# 4x_0805.net
KiCad netlist of a schematic drawn in EAGLE
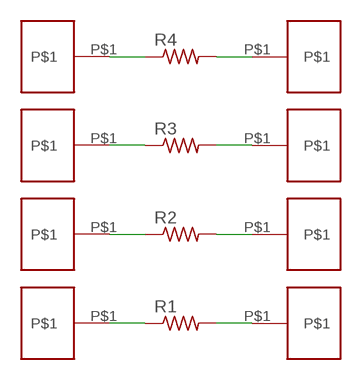
[diagram p0: schematic, sheet 1]

(export (version "E")
  (design (tool "Eeschema 10.0.6"))
  (components
    (comp (ref "R1")
      (value "R-US_R0805")
      (footprint "eagle-import:R0805")
      (libsource (lib "eagle-import") (part "R-US_R0805"))
    )
    (comp (ref "R2")
      (value "R-US_R0805")
      (footprint "eagle-import:R0805")
      (libsource (lib "eagle-import") (part "R-US_R0805"))
    )
    (comp (ref "R3")
      (value "R-US_R0805")
      (footprint "eagle-import:R0805")
      (libsource (lib "eagle-import") (part "R-US_R0805"))
    )
    (comp (ref "R4")
      (value "R-US_R0805")
      (footprint "eagle-import:R0805")
      (libsource (lib "eagle-import") (part "R-US_R0805"))
    )
    (comp (ref "U$1")
      (value "PAD100MIL")
      (footprint "eagle-import:100MIL_PAD")
      (libsource (lib "eagle-import") (part "PAD100MIL"))
    )
    (comp (ref "U$2")
      (value "PAD100MIL")
      (footprint "eagle-import:100MIL_PAD")
      (libsource (lib "eagle-import") (part "PAD100MIL"))
    )
    (comp (ref "U$3")
      (value "PAD100MIL")
      (footprint "eagle-import:100MIL_PAD")
      (libsource (lib "eagle-import") (part "PAD100MIL"))
    )
    (comp (ref "U$4")
      (value "PAD100MIL")
      (footprint "eagle-import:100MIL_PAD")
      (libsource (lib "eagle-import") (part "PAD100MIL"))
    )
    (comp (ref "U$5")
      (value "PAD100MIL")
      (footprint "eagle-import:100MIL_PAD")
      (libsource (lib "eagle-import") (part "PAD100MIL"))
    )
    (comp (ref "U$6")
      (value "PAD100MIL")
      (footprint "eagle-import:100MIL_PAD")
      (libsource (lib "eagle-import") (part "PAD100MIL"))
    )
    (comp (ref "U$7")
      (value "PAD100MIL")
      (footprint "eagle-import:100MIL_PAD")
      (libsource (lib "eagle-import") (part "PAD100MIL"))
    )
    (comp (ref "U$8")
      (value "PAD100MIL")
      (footprint "eagle-import:100MIL_PAD")
      (libsource (lib "eagle-import") (part "PAD100MIL"))
    )
  )
  (nets
    (net (code "1") (name "Net-(R1-Pad1)") (class "Default")
      (node (ref "R1") (pin "1") (pinfunction "1_1") (pintype "passive"))
      (node (ref "U$4") (pin "P$1") (pinfunction "P$1_P$1") (pintype "bidirectional"))
    )
    (net (code "2") (name "Net-(R1-Pad2)") (class "Default")
      (node (ref "R1") (pin "2") (pinfunction "2_2") (pintype "passive"))
      (node (ref "U$8") (pin "P$1") (pinfunction "P$1_P$1") (pintype "bidirectional"))
    )
    (net (code "3") (name "Net-(R2-Pad1)") (class "Default")
      (node (ref "R2") (pin "1") (pinfunction "1_1") (pintype "passive"))
      (node (ref "U$3") (pin "P$1") (pinfunction "P$1_P$1") (pintype "bidirectional"))
    )
    (net (code "4") (name "Net-(R2-Pad2)") (class "Default")
      (node (ref "R2") (pin "2") (pinfunction "2_2") (pintype "passive"))
      (node (ref "U$7") (pin "P$1") (pinfunction "P$1_P$1") (pintype "bidirectional"))
    )
    (net (code "5") (name "Net-(R3-Pad1)") (class "Default")
      (node (ref "R3") (pin "1") (pinfunction "1_1") (pintype "passive"))
      (node (ref "U$2") (pin "P$1") (pinfunction "P$1_P$1") (pintype "bidirectional"))
    )
    (net (code "6") (name "Net-(R3-Pad2)") (class "Default")
      (node (ref "R3") (pin "2") (pinfunction "2_2") (pintype "passive"))
      (node (ref "U$6") (pin "P$1") (pinfunction "P$1_P$1") (pintype "bidirectional"))
    )
    (net (code "7") (name "Net-(R4-Pad1)") (class "Default")
      (node (ref "R4") (pin "1") (pinfunction "1_1") (pintype "passive"))
      (node (ref "U$1") (pin "P$1") (pinfunction "P$1_P$1") (pintype "bidirectional"))
    )
    (net (code "8") (name "Net-(R4-Pad2)") (class "Default")
      (node (ref "R4") (pin "2") (pinfunction "2_2") (pintype "passive"))
      (node (ref "U$5") (pin "P$1") (pinfunction "P$1_P$1") (pintype "bidirectional"))
    )
  )
)
